# Classes.net
KiCad netlist of a schematic drawn in Altium Designer
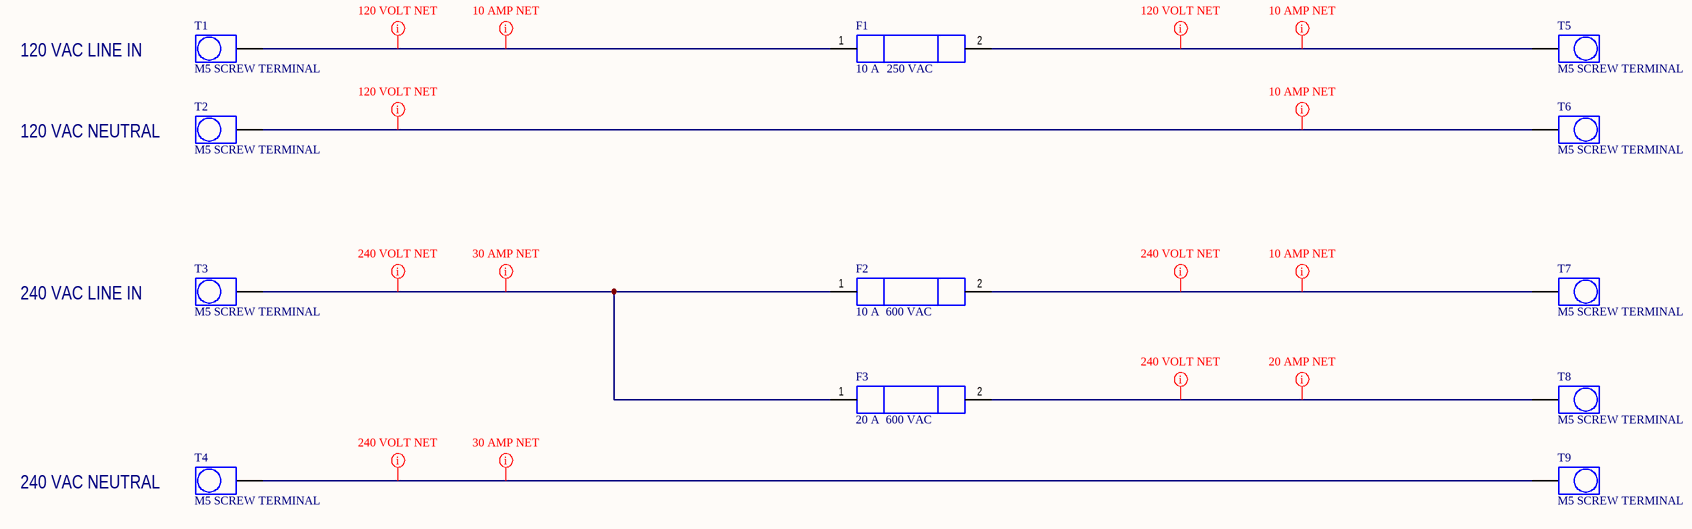
[diagram p0: Classes.SchDoc]

(export (version "E")
  (design (tool "Eeschema 10.0.6"))
  (components
    (comp (ref "F1")
      (value "10 A")
      (footprint "1/4 FUSE")
      (description "10 AMP 250 VAC FUSE")
      (fields (field (name "PART NUMBER") "GBB-10-R") (field (name "VOLTAGE_RATING") "250 VAC"))
      (libsource (lib "Schlib1") (part "10 AMP 250 VAC FUSE"))
    )
    (comp (ref "F2")
      (value "10 A")
      (footprint "13/32 FUSE")
      (description "10 AMP 600 VAC FUSE")
      (fields (field (name "PART NUMBER") "KTK-R-10") (field (name "VOLTAGE_RATING") "600 VAC"))
      (libsource (lib "Schlib1") (part "10 AMP 600 VAC FUSE"))
    )
    (comp (ref "F3")
      (value "20 A")
      (footprint "13/32 FUSE")
      (description "20 AMP 600 VAC FUSE")
      (fields (field (name "PART NUMBER") "KTK-R-20") (field (name "VOLTAGE_RATING") "600 VAC"))
      (libsource (lib "Schlib1") (part "20 AMP 600 VAC FUSE"))
    )
    (comp (ref "T1")
      (value "M5 SCREW TERMINAL")
      (footprint "M5 TERMINAL")
      (libsource (lib "Schlib1") (part "TERMINAL"))
    )
    (comp (ref "T2")
      (value "M5 SCREW TERMINAL")
      (footprint "M5 TERMINAL")
      (libsource (lib "Schlib1") (part "TERMINAL"))
    )
    (comp (ref "T3")
      (value "M5 SCREW TERMINAL")
      (footprint "M5 TERMINAL")
      (libsource (lib "Schlib1") (part "TERMINAL"))
    )
    (comp (ref "T4")
      (value "M5 SCREW TERMINAL")
      (footprint "M5 TERMINAL")
      (libsource (lib "Schlib1") (part "TERMINAL"))
    )
    (comp (ref "T5")
      (value "M5 SCREW TERMINAL")
      (footprint "M5 TERMINAL")
      (libsource (lib "Schlib1") (part "TERMINAL"))
    )
    (comp (ref "T6")
      (value "M5 SCREW TERMINAL")
      (footprint "M5 TERMINAL")
      (libsource (lib "Schlib1") (part "TERMINAL"))
    )
    (comp (ref "T7")
      (value "M5 SCREW TERMINAL")
      (footprint "M5 TERMINAL")
      (libsource (lib "Schlib1") (part "TERMINAL"))
    )
    (comp (ref "T8")
      (value "M5 SCREW TERMINAL")
      (footprint "M5 TERMINAL")
      (libsource (lib "Schlib1") (part "TERMINAL"))
    )
    (comp (ref "T9")
      (value "M5 SCREW TERMINAL")
      (footprint "M5 TERMINAL")
      (libsource (lib "Schlib1") (part "TERMINAL"))
    )
  )
  (nets
    (net (code "1") (name "Net-(F1-Pad1)") (class "Default")
      (node (ref "F1") (pin "1") (pinfunction "1_1") (pintype "passive"))
      (node (ref "T1") (pin "1") (pinfunction "1_1") (pintype "passive"))
    )
    (net (code "2") (name "Net-(F1-Pad2)") (class "Default")
      (node (ref "F1") (pin "2") (pinfunction "2_2") (pintype "passive"))
      (node (ref "T5") (pin "1") (pinfunction "1_1") (pintype "passive"))
    )
    (net (code "3") (name "Net-(F2-Pad1)") (class "Default")
      (node (ref "F2") (pin "1") (pinfunction "1_1") (pintype "passive"))
      (node (ref "F3") (pin "1") (pinfunction "1_1") (pintype "passive"))
      (node (ref "T3") (pin "1") (pinfunction "1_1") (pintype "passive"))
    )
    (net (code "4") (name "Net-(F2-Pad2)") (class "Default")
      (node (ref "F2") (pin "2") (pinfunction "2_2") (pintype "passive"))
      (node (ref "T7") (pin "1") (pinfunction "1_1") (pintype "passive"))
    )
    (net (code "5") (name "Net-(F3-Pad2)") (class "Default")
      (node (ref "F3") (pin "2") (pinfunction "2_2") (pintype "passive"))
      (node (ref "T8") (pin "1") (pinfunction "1_1") (pintype "passive"))
    )
    (net (code "6") (name "Net-(T2-Pad1)") (class "Default")
      (node (ref "T2") (pin "1") (pinfunction "1_1") (pintype "passive"))
      (node (ref "T6") (pin "1") (pinfunction "1_1") (pintype "passive"))
    )
    (net (code "7") (name "Net-(T4-Pad1)") (class "Default")
      (node (ref "T4") (pin "1") (pinfunction "1_1") (pintype "passive"))
      (node (ref "T9") (pin "1") (pinfunction "1_1") (pintype "passive"))
    )
  )
)
